# Power_supply.net
KiCad netlist of a schematic drawn in Altium Designer
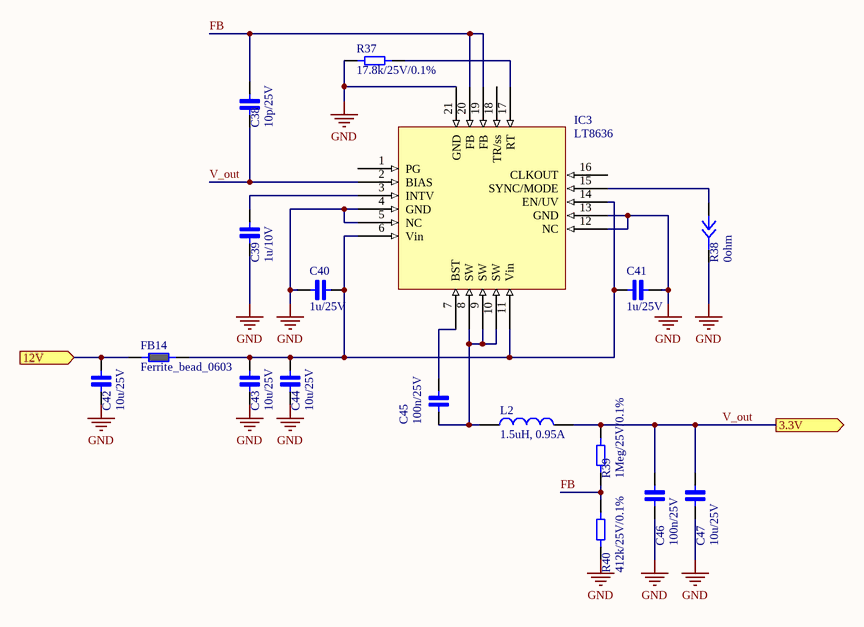
[diagram p0: Power_supply.SchDoc]

(export (version "E")
  (design (tool "Eeschema 10.0.6"))
  (components
    (comp (ref "C38")
      (value "10p/25V")
      (footprint "CAP_0603")
      (description "Ceramic Capacitor 10p / 0603 / 25V / ±5%, Wurth Elektronik MLCC")
      (libsource (lib "Cubesat_lib") (part "Cap_0603_10p"))
    )
    (comp (ref "C39")
      (value "1u/10V")
      (footprint "CAP_0603")
      (description "Ceramic Capacitor 1uF / 0603 / 10V / ±5%, Wurth Elektronik MLCC")
      (libsource (lib "Cubesat_lib") (part "Cap_0603_1u"))
    )
    (comp (ref "C40")
      (value "1u/25V")
      (footprint "CAP_0603")
      (description "Ceramic Capacitor 1uF / 0603 / 25V / ±5%, Wurth Elektronik MLCC")
      (libsource (lib "Cubesat_lib") (part "Cap_0603_1u_25v"))
    )
    (comp (ref "C41")
      (value "1u/25V")
      (footprint "CAP_0603")
      (description "Ceramic Capacitor 1uF / 0603 / 25V / ±5%, Wurth Elektronik MLCC")
      (libsource (lib "Cubesat_lib") (part "Cap_0603_1u_25v"))
    )
    (comp (ref "C42")
      (value "10u/25V")
      (footprint "CAP_1210")
      (description "Multilayer Ceramic Capacitors MLCC - SMD/SMT 1210 10uF 25volts *Derate Voltage/Temp")
      (fields
        (field (name "MANUFACTURER") "Murata")
        (field (name "MANUFACTURER PART NUMBER") "GRM32ER71K475KE14L")
      )
      (libsource (lib "Cubesat_lib") (part "Cap_1210_10u"))
    )
    (comp (ref "C43")
      (value "10u/25V")
      (footprint "CAP_1210")
      (description "Multilayer Ceramic Capacitors MLCC - SMD/SMT 1210 10uF 25volts *Derate Voltage/Temp")
      (fields
        (field (name "MANUFACTURER") "Murata")
        (field (name "MANUFACTURER PART NUMBER") "GRM32ER71K475KE14L")
      )
      (libsource (lib "Cubesat_lib") (part "Cap_1210_10u"))
    )
    (comp (ref "C44")
      (value "10u/25V")
      (footprint "CAP_1210")
      (description "Multilayer Ceramic Capacitors MLCC - SMD/SMT 1210 10uF 25volts *Derate Voltage/Temp")
      (fields
        (field (name "MANUFACTURER") "Murata")
        (field (name "MANUFACTURER PART NUMBER") "GRM32ER71K475KE14L")
      )
      (libsource (lib "Cubesat_lib") (part "Cap_1210_10u"))
    )
    (comp (ref "C45")
      (value "100n/25V")
      (footprint "CAP_0603")
      (description "Ceramic Capacitor 100n / 0603 / 25V / ±5%, Wurth Elektronik MLCC")
      (libsource (lib "") (part "Cap_0603_100n_1"))
    )
    (comp (ref "C46")
      (value "100n/25V")
      (footprint "CAP_0603")
      (description "Ceramic Capacitor 100n / 0603 / 25V / ±5%, Wurth Elektronik MLCC")
      (libsource (lib "Cubesat_lib") (part "Cap_0603_100n"))
    )
    (comp (ref "C47")
      (value "10u/25V")
      (footprint "CAP_1210")
      (description "Multilayer Ceramic Capacitors MLCC - SMD/SMT 1210 10uF 25volts *Derate Voltage/Temp")
      (fields
        (field (name "MANUFACTURER") "Murata")
        (field (name "MANUFACTURER PART NUMBER") "GRM32ER71K475KE14L")
      )
      (libsource (lib "Cubesat_lib") (part "Cap_1210_10u"))
    )
    (comp (ref "FB14")
      (value "Ferrite_bead_0603")
      (footprint "Ferrite_0603")
      (description "Ferrite bead")
      (libsource (lib "Cubesat_lib") (part "Ferrite_bead_0603"))
    )
    (comp (ref "IC3")
      (value "LT8636")
      (footprint "LQFN20")
      (description "42V, 5A/7A Peak Synchronous Step-Down\r\n Silent Switcher with 2.5µA Quiescent Current")
      (libsource (lib "Cubesat_lib") (part "LT8636"))
    )
    (comp (ref "L2")
      (value "1.5uH, 0.95A")
      (footprint "WE-MAPI_1610")
      (description "WE-MAPI SMT Power Inductor, size 1610, 1.5uH, 0.95A")
      (fields
        (field (name "MANUFACTURER") "Wurth Elektronik")
        (field (name "MANUFACTURER PART NUMBER") "74438313015")
      )
      (libsource (lib "WE-MAPI_tiny_inductors") (part "74438313015"))
    )
    (comp (ref "R37")
      (value "17.8k/25V/0.1%")
      (footprint "RES_0603")
      (description "Vishay, thin film resistor 17.8k/25V/0.1%")
      (libsource (lib "Cubesat_lib") (part "Res_0603_17.8k"))
    )
    (comp (ref "R38") (value "0ohm") (libsource (lib "Cubesat_lib") (part "Jumper")))
    (comp (ref "R39")
      (value "1Meg/25V/0.1%")
      (footprint "RES_0603")
      (description "Vishay, thin film resistor 1Meg/25V/0.1%")
      (libsource (lib "Cubesat_lib") (part "Res_0603_1Meg"))
    )
    (comp (ref "R40")
      (value "412k/25V/0.1%")
      (footprint "RES_0603")
      (description "Vishay, thin film resistor 412k/25V/0.1%")
      (libsource (lib "Cubesat_lib") (part "Res_0603_412k"))
    )
  )
  (nets
    (net (code "1") (name "/12V") (class "Default")
      (node (ref "C42") (pin "2") (pinfunction "2_2") (pintype "passive"))
      (node (ref "FB14") (pin "2") (pinfunction "2_2") (pintype "passive"))
    )
    (net (code "2") (name "/FB") (class "Default")
      (node (ref "C38") (pin "2") (pinfunction "2_2") (pintype "passive"))
      (node (ref "IC3") (pin "19") (pinfunction "FB_19") (pintype "input"))
      (node (ref "IC3") (pin "20") (pinfunction "FB_20") (pintype "input"))
      (node (ref "R39") (pin "2") (pinfunction "2_2") (pintype "passive"))
      (node (ref "R40") (pin "2") (pinfunction "2_2") (pintype "passive"))
    )
    (net (code "3") (name "/V_out") (class "Default")
      (node (ref "C38") (pin "2") (pinfunction "2_2") (pintype "passive"))
      (node (ref "C46") (pin "2") (pinfunction "2_2") (pintype "passive"))
      (node (ref "C47") (pin "2") (pinfunction "2_2") (pintype "passive"))
      (node (ref "IC3") (pin "2") (pinfunction "BIAS_2") (pintype "input"))
      (node (ref "L2") (pin "2") (pinfunction "2_2") (pintype "passive"))
      (node (ref "R39") (pin "2") (pinfunction "2_2") (pintype "passive"))
    )
    (net (code "4") (name "GND") (class "Default")
      (node (ref "C39") (pin "2") (pinfunction "2_2") (pintype "passive"))
      (node (ref "C40") (pin "2") (pinfunction "2_2") (pintype "passive"))
      (node (ref "C41") (pin "2") (pinfunction "2_2") (pintype "passive"))
      (node (ref "C42") (pin "2") (pinfunction "2_2") (pintype "passive"))
      (node (ref "C43") (pin "2") (pinfunction "2_2") (pintype "passive"))
      (node (ref "C44") (pin "2") (pinfunction "2_2") (pintype "passive"))
      (node (ref "C46") (pin "2") (pinfunction "2_2") (pintype "passive"))
      (node (ref "C47") (pin "2") (pinfunction "2_2") (pintype "passive"))
      (node (ref "IC3") (pin "12") (pinfunction "NC_12") (pintype "input"))
      (node (ref "IC3") (pin "13") (pinfunction "GND_13") (pintype "input"))
      (node (ref "IC3") (pin "21") (pinfunction "GND_21") (pintype "input"))
      (node (ref "IC3") (pin "4") (pinfunction "GND_4") (pintype "input"))
      (node (ref "IC3") (pin "5") (pinfunction "NC_5") (pintype "input"))
      (node (ref "R37") (pin "2") (pinfunction "2_2") (pintype "passive"))
      (node (ref "R38") (pin "2") (pinfunction "2_2") (pintype "passive"))
      (node (ref "R40") (pin "2") (pinfunction "2_2") (pintype "passive"))
    )
    (net (code "5") (name "Net-(C45-Pad2)") (class "Default")
      (node (ref "C45") (pin "2") (pinfunction "2_2") (pintype "passive"))
      (node (ref "IC3") (pin "10") (pinfunction "SW_10") (pintype "input"))
      (node (ref "IC3") (pin "8") (pinfunction "SW_8") (pintype "input"))
      (node (ref "IC3") (pin "9") (pinfunction "SW_9") (pintype "input"))
      (node (ref "L2") (pin "1") (pinfunction "1_1") (pintype "passive"))
    )
    (net (code "6") (name "Net-(IC3-BST)") (class "Default")
      (node (ref "C45") (pin "2") (pinfunction "2_2") (pintype "passive"))
      (node (ref "IC3") (pin "7") (pinfunction "BST_7") (pintype "input"))
    )
    (net (code "7") (name "Net-(IC3-EN{slash}UV)") (class "Default")
      (node (ref "C40") (pin "2") (pinfunction "2_2") (pintype "passive"))
      (node (ref "C41") (pin "2") (pinfunction "2_2") (pintype "passive"))
      (node (ref "C43") (pin "2") (pinfunction "2_2") (pintype "passive"))
      (node (ref "C44") (pin "2") (pinfunction "2_2") (pintype "passive"))
      (node (ref "FB14") (pin "2") (pinfunction "2_2") (pintype "passive"))
      (node (ref "IC3") (pin "11") (pinfunction "Vin_11") (pintype "input"))
      (node (ref "IC3") (pin "14") (pinfunction "EN/UV_14") (pintype "input"))
      (node (ref "IC3") (pin "6") (pinfunction "Vin_6") (pintype "input"))
    )
    (net (code "8") (name "Net-(IC3-INTV)") (class "Default")
      (node (ref "C39") (pin "2") (pinfunction "2_2") (pintype "passive"))
      (node (ref "IC3") (pin "3") (pinfunction "INTV_3") (pintype "input"))
    )
    (net (code "9") (name "Net-(IC3-RT)") (class "Default")
      (node (ref "IC3") (pin "17") (pinfunction "RT_17") (pintype "input"))
      (node (ref "R37") (pin "2") (pinfunction "2_2") (pintype "passive"))
    )
    (net (code "10") (name "Net-(IC3-SYNC{slash}MODE)") (class "Default")
      (node (ref "IC3") (pin "15") (pinfunction "SYNC/MODE_15") (pintype "input"))
      (node (ref "R38") (pin "2") (pinfunction "2_2") (pintype "passive"))
    )
    (net (code "11") (name "unconnected-(IC3-CLKOUT-Pad16)") (class "Default")
      (node (ref "IC3") (pin "16") (pinfunction "CLKOUT_16") (pintype "input"))
    )
    (net (code "12") (name "unconnected-(IC3-PG-Pad1)") (class "Default")
      (node (ref "IC3") (pin "1") (pinfunction "PG_1") (pintype "input"))
    )
    (net (code "13") (name "unconnected-(IC3-TR{slash}ss-Pad18)") (class "Default")
      (node (ref "IC3") (pin "18") (pinfunction "TR/ss_18") (pintype "input"))
    )
  )
)
